# 9250.net
KiCad netlist of a schematic drawn in EAGLE
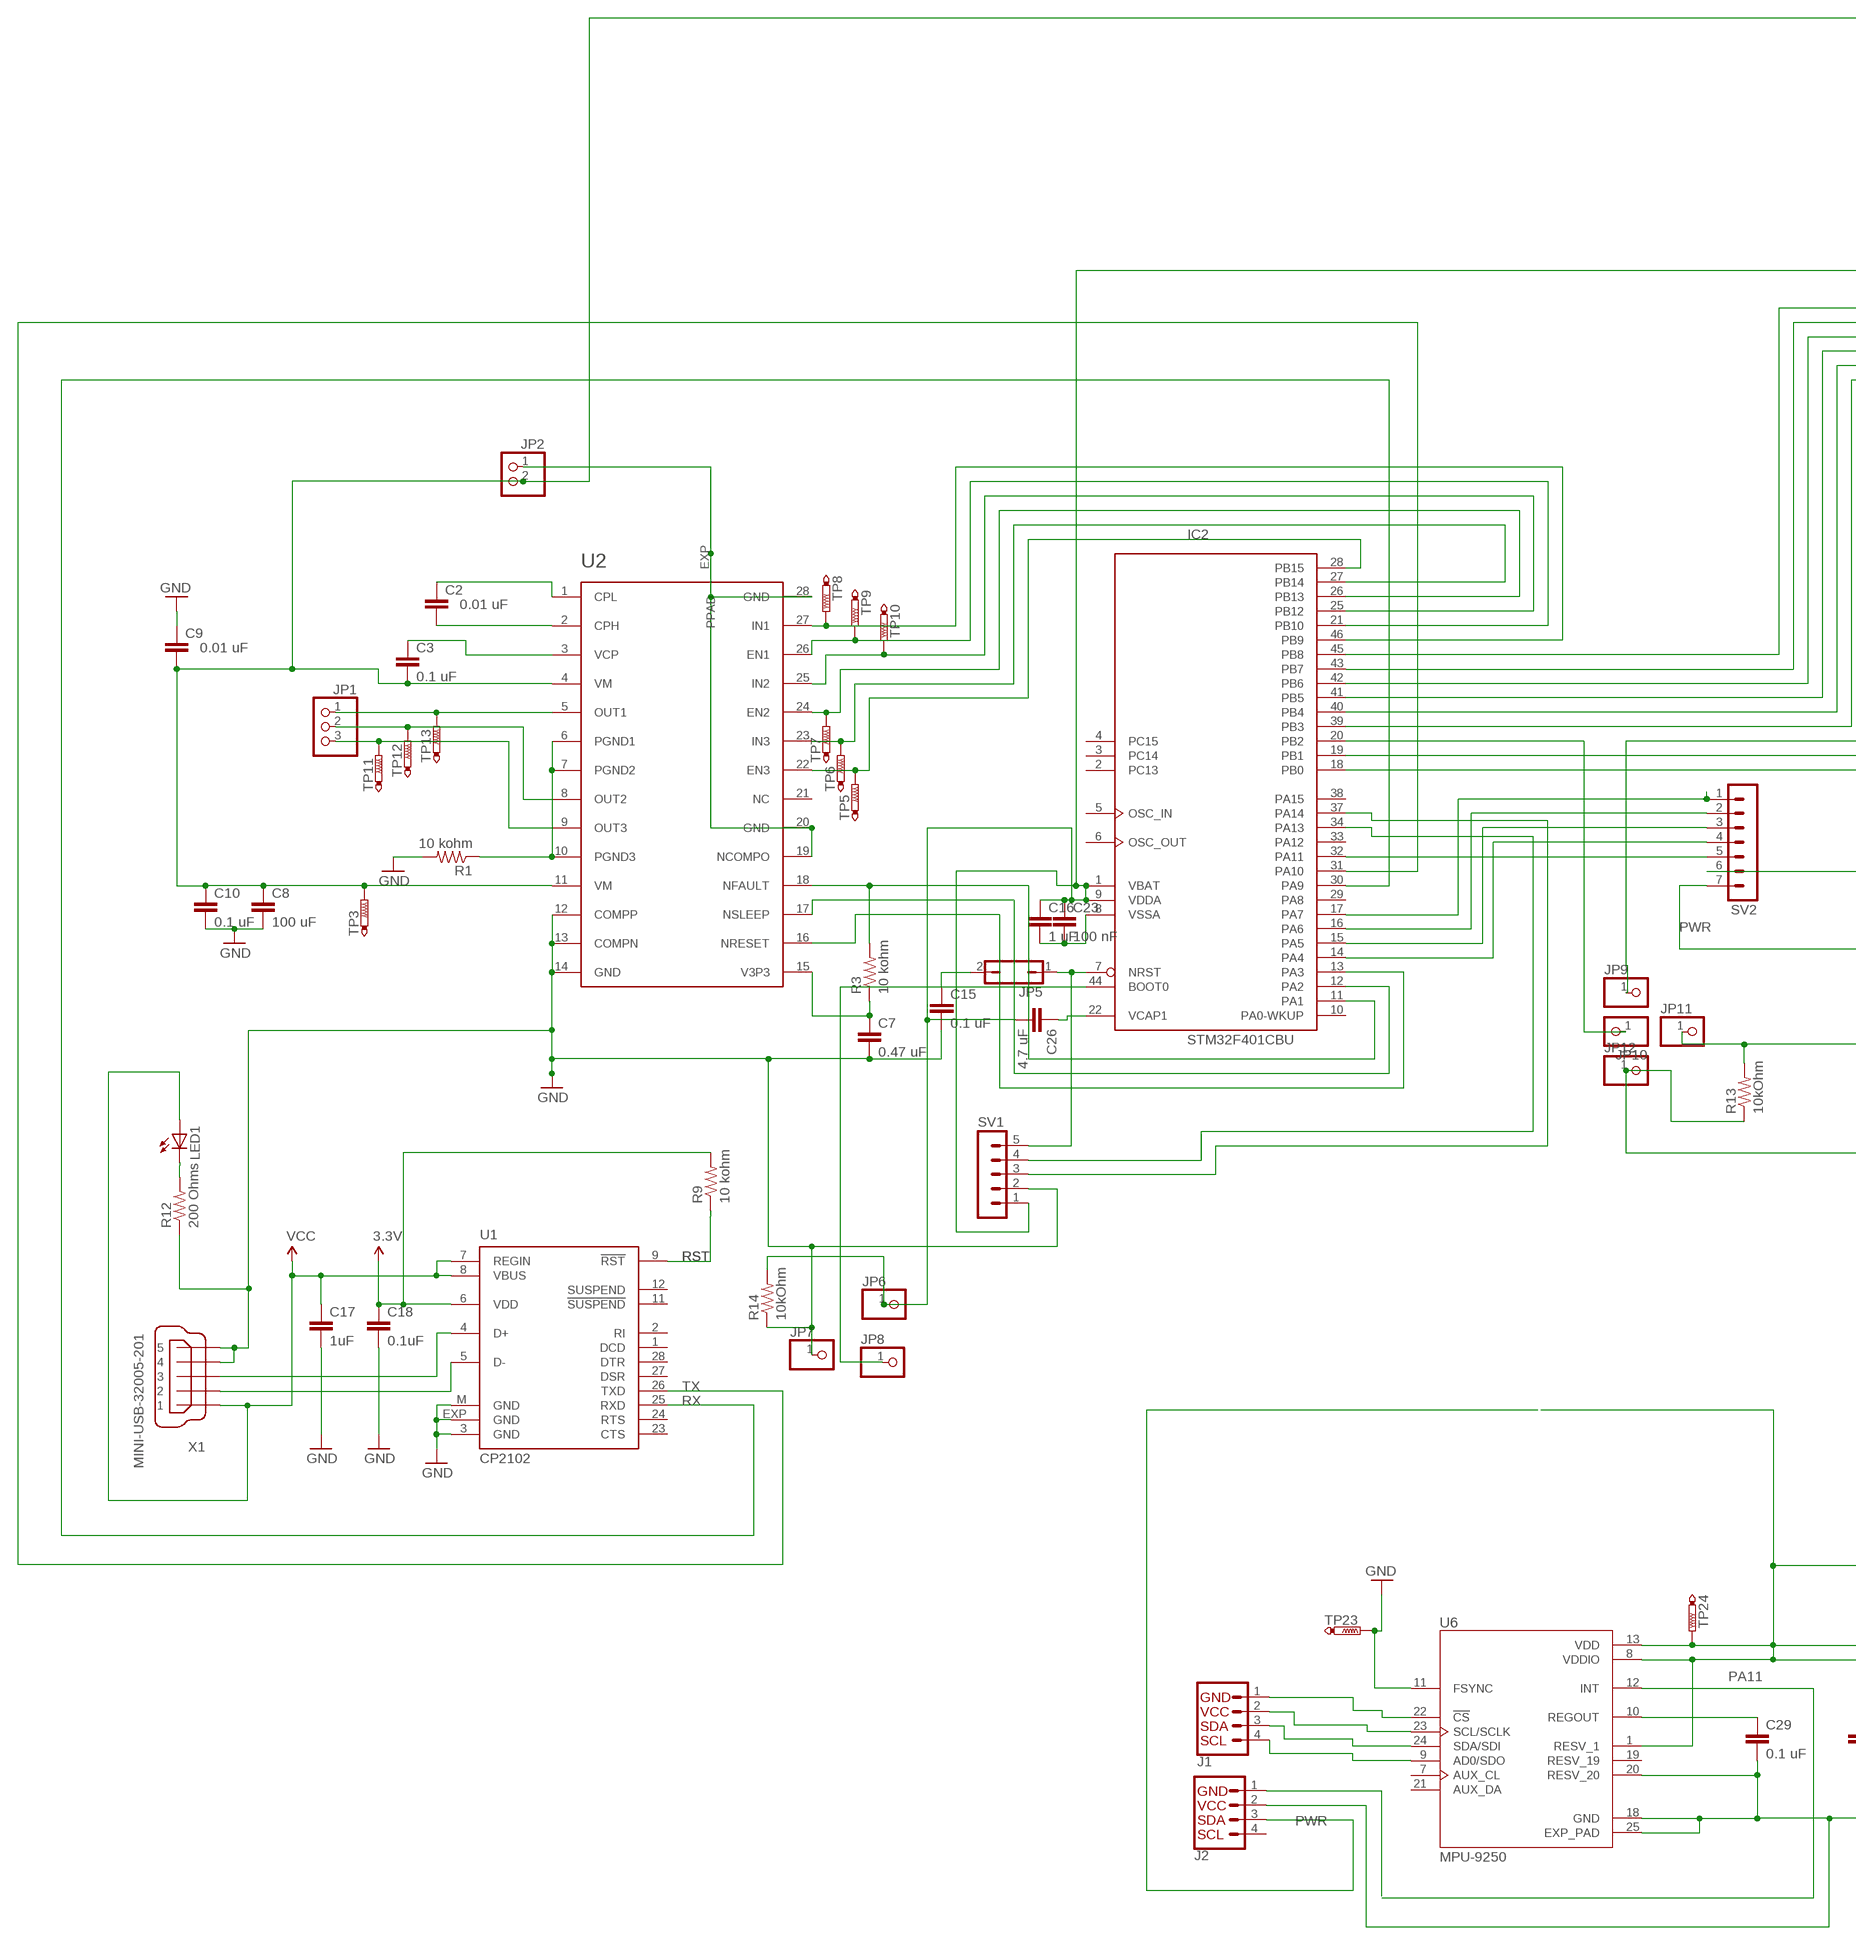
[diagram p0: schematic, sheet 1, part 1 of 2]
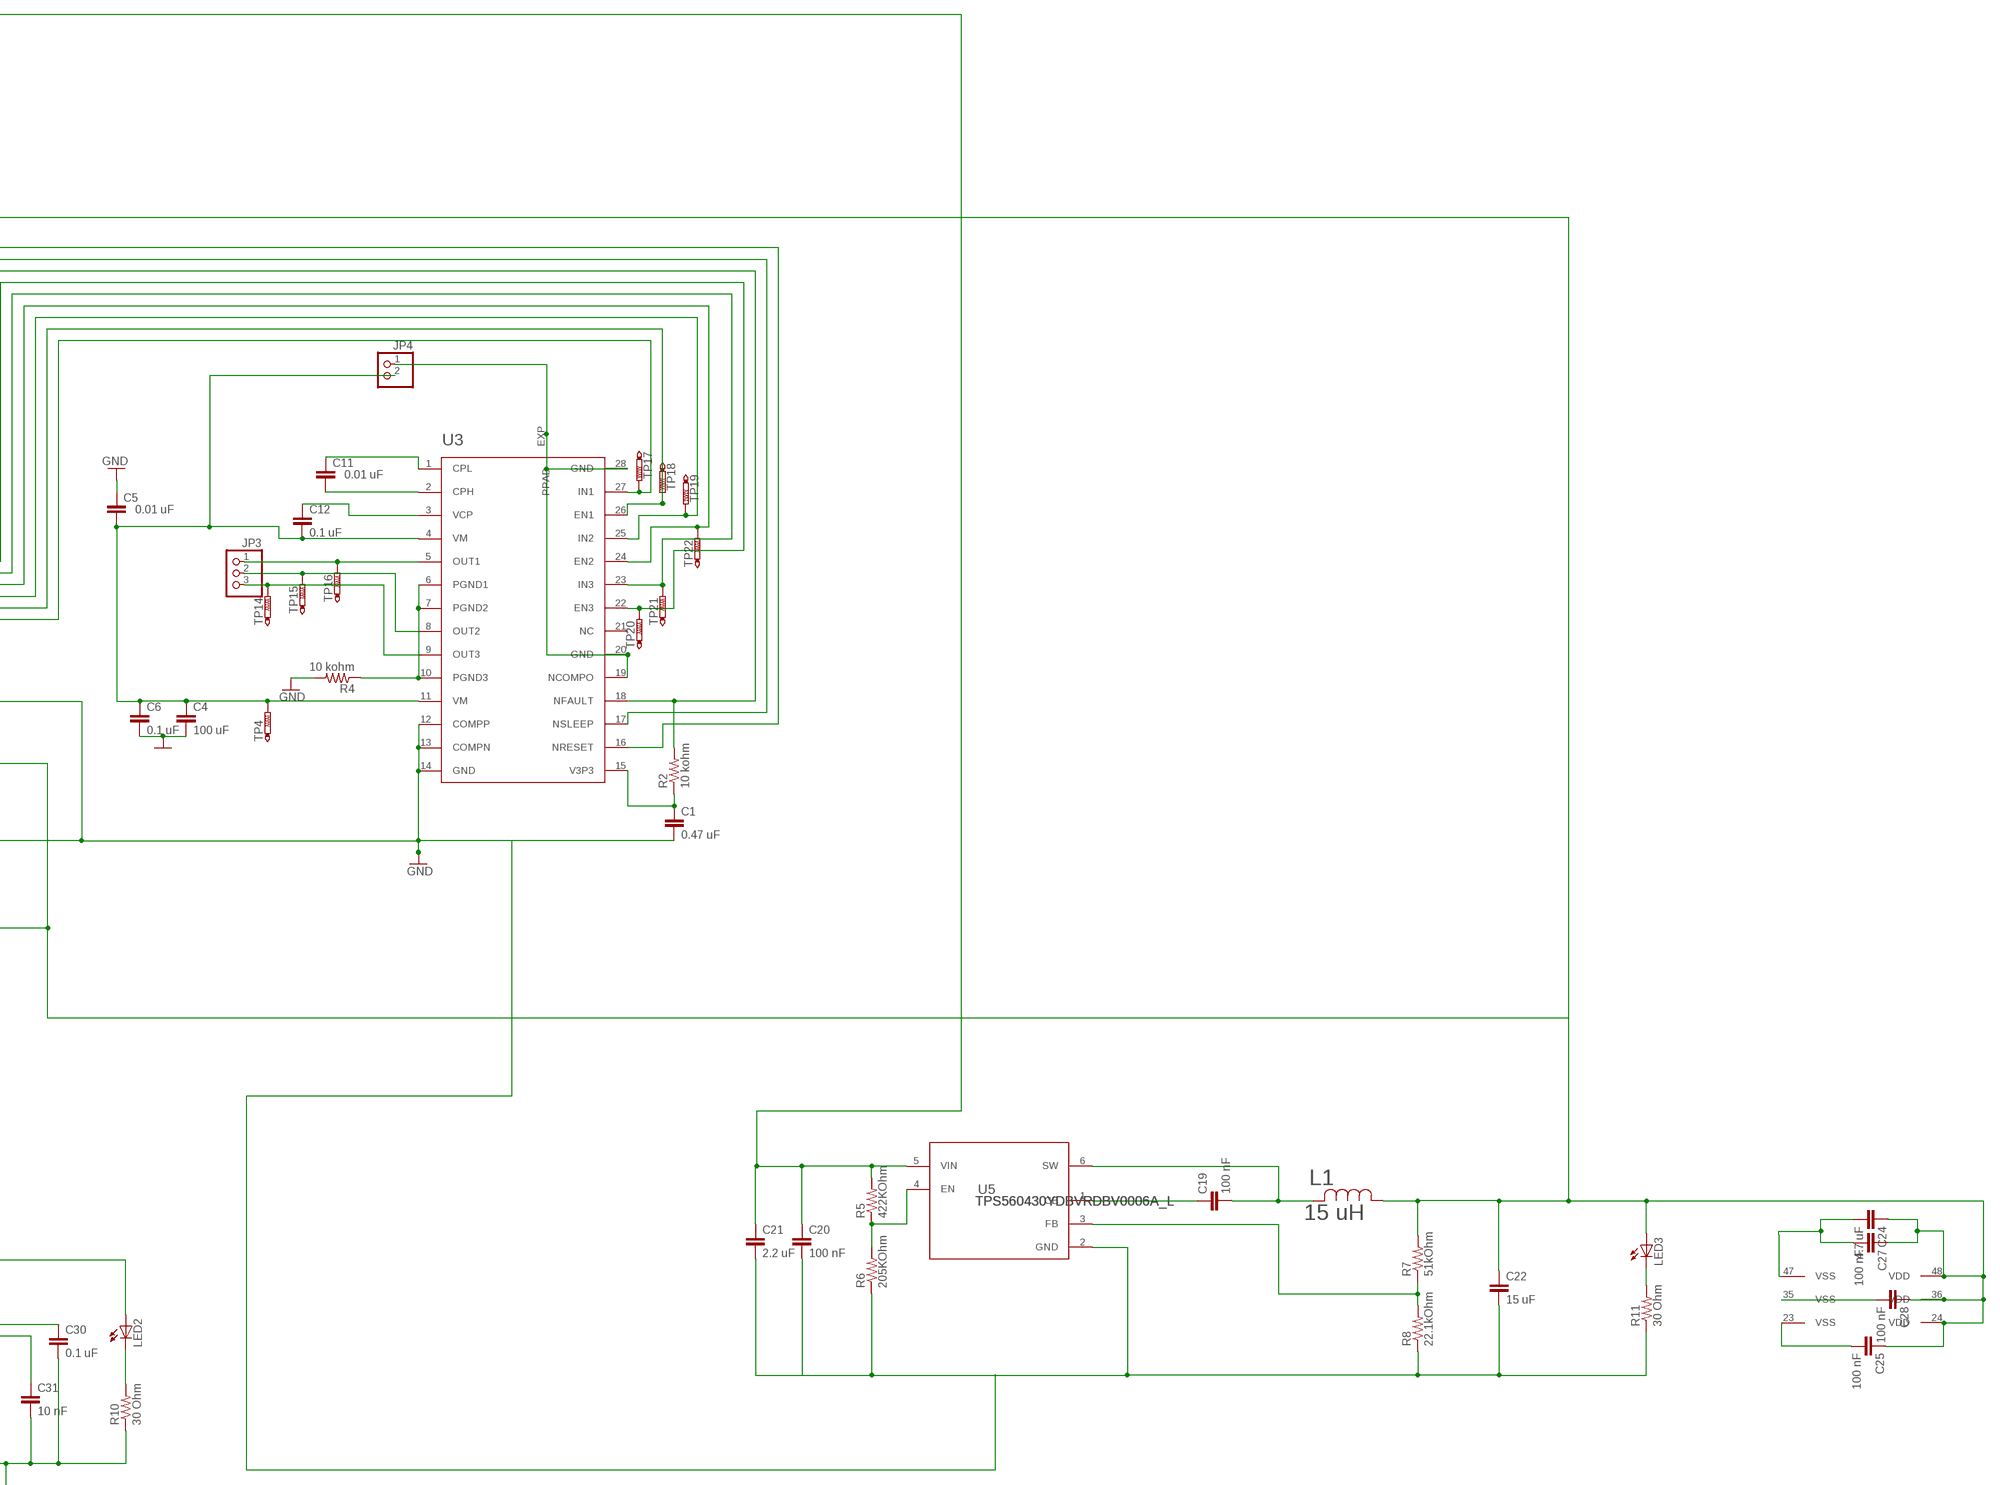
[diagram p1: schematic, sheet 1, part 2 of 2]

(export (version "E")
  (design (tool "Eeschema 10.0.6"))
  (components
    (comp (ref "C1")
      (value "0.47 uF")
      (footprint "eagle-import:C1210K")
      (libsource (lib "eagle-import") (part "C-EUC1210K"))
    )
    (comp (ref "C2")
      (value "0.01 uF")
      (footprint "eagle-import:C1210K")
      (libsource (lib "eagle-import") (part "C-EUC1210K"))
    )
    (comp (ref "C3")
      (value "0.1 uF")
      (footprint "eagle-import:C1210K")
      (libsource (lib "eagle-import") (part "C-EUC1210K"))
    )
    (comp (ref "C4")
      (value "100 uF")
      (footprint "eagle-import:C1210K")
      (libsource (lib "eagle-import") (part "C-EUC1210K"))
    )
    (comp (ref "C5")
      (value "0.01 uF")
      (footprint "eagle-import:C1210K")
      (libsource (lib "eagle-import") (part "C-EUC1210K"))
    )
    (comp (ref "C6")
      (value "0.1 uF")
      (footprint "eagle-import:C1210K")
      (libsource (lib "eagle-import") (part "C-EUC1210K"))
    )
    (comp (ref "C7")
      (value "0.47 uF")
      (footprint "eagle-import:C1210K")
      (libsource (lib "eagle-import") (part "C-EUC1210K"))
    )
    (comp (ref "C8")
      (value "100 uF")
      (footprint "eagle-import:C1210K")
      (libsource (lib "eagle-import") (part "C-EUC1210K"))
    )
    (comp (ref "C9")
      (value "0.01 uF")
      (footprint "eagle-import:C1210K")
      (libsource (lib "eagle-import") (part "C-EUC1210K"))
    )
    (comp (ref "C10")
      (value "0.1 uF")
      (footprint "eagle-import:C1210K")
      (libsource (lib "eagle-import") (part "C-EUC1210K"))
    )
    (comp (ref "C11")
      (value "0.01 uF")
      (footprint "eagle-import:C1210K")
      (libsource (lib "eagle-import") (part "C-EUC1210K"))
    )
    (comp (ref "C12")
      (value "0.1 uF")
      (footprint "eagle-import:C1210K")
      (libsource (lib "eagle-import") (part "C-EUC1210K"))
    )
    (comp (ref "C15")
      (value "0.1 uF")
      (footprint "eagle-import:C1210K")
      (libsource (lib "eagle-import") (part "C-EUC1210K"))
    )
    (comp (ref "C16")
      (value "1 uF")
      (footprint "eagle-import:C1210K")
      (libsource (lib "eagle-import") (part "C-EUC1210K"))
    )
    (comp (ref "C17")
      (value "1uF")
      (footprint "eagle-import:0603")
      (libsource (lib "eagle-import") (part "CAP0603"))
    )
    (comp (ref "C18")
      (value "0.1uF")
      (footprint "eagle-import:0603")
      (libsource (lib "eagle-import") (part "CAP0603"))
    )
    (comp (ref "C19")
      (value "100 nF")
      (footprint "eagle-import:C0402K")
      (libsource (lib "eagle-import") (part "C-EUC0402K"))
    )
    (comp (ref "C20")
      (value "100 nF")
      (footprint "eagle-import:C0402K")
      (libsource (lib "eagle-import") (part "C-EUC0402K"))
    )
    (comp (ref "C21")
      (value "2.2 uF")
      (footprint "eagle-import:C0402K")
      (libsource (lib "eagle-import") (part "C-EUC0402K"))
    )
    (comp (ref "C22")
      (value "15 uF")
      (footprint "eagle-import:C0402K")
      (libsource (lib "eagle-import") (part "C-EUC0402K"))
    )
    (comp (ref "C23")
      (value "100 nF")
      (footprint "eagle-import:C1210K")
      (libsource (lib "eagle-import") (part "C-EUC1210K"))
    )
    (comp (ref "C24")
      (value "4.7 uF")
      (footprint "eagle-import:C1210K")
      (libsource (lib "eagle-import") (part "C-EUC1210K"))
    )
    (comp (ref "C25")
      (value "100 nF")
      (footprint "eagle-import:C1210K")
      (libsource (lib "eagle-import") (part "C-EUC1210K"))
    )
    (comp (ref "C26")
      (value "4.7 uF")
      (footprint "eagle-import:C1210K")
      (libsource (lib "eagle-import") (part "C-EUC1210K"))
    )
    (comp (ref "C27")
      (value "100 nF")
      (footprint "eagle-import:C1210K")
      (libsource (lib "eagle-import") (part "C-EUC1210K"))
    )
    (comp (ref "C28")
      (value "100 nF")
      (footprint "eagle-import:C1210K")
      (libsource (lib "eagle-import") (part "C-EUC1210K"))
    )
    (comp (ref "C29")
      (value "0.1 uF")
      (footprint "eagle-import:C025-025X050")
      (libsource (lib "eagle-import") (part "C-EU025-025X050"))
    )
    (comp (ref "C30")
      (value "0.1 uF")
      (footprint "eagle-import:C025-025X050")
      (libsource (lib "eagle-import") (part "C-EU025-025X050"))
    )
    (comp (ref "C31")
      (value "10 nF")
      (footprint "eagle-import:C025-025X050")
      (libsource (lib "eagle-import") (part "C-EU025-025X050"))
    )
    (comp (ref "IC2")
      (value "STM32F401CBU")
      (footprint "eagle-import:UFQFPN48")
      (libsource (lib "eagle-import") (part "STM32F401CUB"))
    )
    (comp (ref "J1")
      (value "QWIIC_CONNECTORJS-1MM")
      (footprint "eagle-import:1X04_1MM_RA")
      (libsource (lib "eagle-import") (part "QWIIC_CONNECTORJS-1MM"))
    )
    (comp (ref "J2")
      (value "QWIIC_CONNECTORJS-1MM")
      (footprint "eagle-import:1X04_1MM_RA")
      (libsource (lib "eagle-import") (part "QWIIC_CONNECTORJS-1MM"))
    )
    (comp (ref "JP1")
      (value "PINHD-1X3/90")
      (footprint "eagle-import:1X03_90")
      (libsource (lib "eagle-import") (part "PINHD-1X3/90"))
    )
    (comp (ref "JP2")
      (value "PINHD-1X2/90")
      (footprint "eagle-import:1X02_90")
      (libsource (lib "eagle-import") (part "PINHD-1X2/90"))
    )
    (comp (ref "JP3")
      (value "PINHD-1X3/90")
      (footprint "eagle-import:1X03_90")
      (libsource (lib "eagle-import") (part "PINHD-1X3/90"))
    )
    (comp (ref "JP4")
      (value "PINHD-1X2/90")
      (footprint "eagle-import:1X02_90")
      (libsource (lib "eagle-import") (part "PINHD-1X2/90"))
    )
    (comp (ref "JP5")
      (value "JP1Q")
      (footprint "eagle-import:JP1")
      (libsource (lib "eagle-import") (part "JP1Q"))
    )
    (comp (ref "JP6")
      (value "PINHD-1X1")
      (footprint "eagle-import:1X01")
      (libsource (lib "eagle-import") (part "PINHD-1X1"))
    )
    (comp (ref "JP7")
      (value "PINHD-1X1")
      (footprint "eagle-import:1X01")
      (libsource (lib "eagle-import") (part "PINHD-1X1"))
    )
    (comp (ref "JP8")
      (value "PINHD-1X1")
      (footprint "eagle-import:1X01")
      (libsource (lib "eagle-import") (part "PINHD-1X1"))
    )
    (comp (ref "JP9")
      (value "PINHD-1X1")
      (footprint "eagle-import:1X01")
      (libsource (lib "eagle-import") (part "PINHD-1X1"))
    )
    (comp (ref "JP10")
      (value "PINHD-1X1")
      (footprint "eagle-import:1X01")
      (libsource (lib "eagle-import") (part "PINHD-1X1"))
    )
    (comp (ref "JP11")
      (value "PINHD-1X1")
      (footprint "eagle-import:1X01")
      (libsource (lib "eagle-import") (part "PINHD-1X1"))
    )
    (comp (ref "JP12")
      (value "PINHD-1X1")
      (footprint "eagle-import:1X01")
      (libsource (lib "eagle-import") (part "PINHD-1X1"))
    )
    (comp (ref "L1")
      (value "15 uH")
      (footprint "eagle-import:IND_BOURNS_SRN3015")
      (fields (field (name "MANUFACTURER_PART_NUMBER") "SRN3015150M"))
      (libsource (lib "eagle-import") (part "SRN3015-150M"))
    )
    (comp (ref "LED1")
      (value "LED_ESML0603")
      (footprint "eagle-import:LED_SML0603")
      (libsource (lib "eagle-import") (part "LED_ESML0603"))
    )
    (comp (ref "LED2")
      (value "LED_ESML0603")
      (footprint "eagle-import:LED_SML0603")
      (libsource (lib "eagle-import") (part "LED_ESML0603"))
    )
    (comp (ref "LED3")
      (value "LED_ESML0603")
      (footprint "eagle-import:LED_SML0603")
      (libsource (lib "eagle-import") (part "LED_ESML0603"))
    )
    (comp (ref "R1")
      (value "10 kohm")
      (footprint "eagle-import:M2012")
      (libsource (lib "eagle-import") (part "R-US_M2012"))
    )
    (comp (ref "R2")
      (value "10 kohm")
      (footprint "eagle-import:M2012")
      (libsource (lib "eagle-import") (part "R-US_M2012"))
    )
    (comp (ref "R3")
      (value "10 kohm")
      (footprint "eagle-import:M2012")
      (libsource (lib "eagle-import") (part "R-US_M2012"))
    )
    (comp (ref "R4")
      (value "10 kohm")
      (footprint "eagle-import:M2012")
      (libsource (lib "eagle-import") (part "R-US_M2012"))
    )
    (comp (ref "R5")
      (value "422KOhm")
      (footprint "eagle-import:M0805")
      (libsource (lib "eagle-import") (part "R-US_M0805"))
    )
    (comp (ref "R6")
      (value "205KOhm")
      (footprint "eagle-import:M0805")
      (libsource (lib "eagle-import") (part "R-US_M0805"))
    )
    (comp (ref "R7")
      (value "51kOhm")
      (footprint "eagle-import:M0805")
      (libsource (lib "eagle-import") (part "R-US_M0805"))
    )
    (comp (ref "R8")
      (value "22.1kOhm")
      (footprint "eagle-import:M0805")
      (libsource (lib "eagle-import") (part "R-US_M0805"))
    )
    (comp (ref "R9")
      (value "10 kohm")
      (footprint "eagle-import:M2012")
      (libsource (lib "eagle-import") (part "R-US_M2012"))
    )
    (comp (ref "R10")
      (value "30 Ohm")
      (footprint "eagle-import:M0805")
      (libsource (lib "eagle-import") (part "R-US_M0805"))
    )
    (comp (ref "R11")
      (value "30 Ohm")
      (footprint "eagle-import:M0805")
      (libsource (lib "eagle-import") (part "R-US_M0805"))
    )
    (comp (ref "R12")
      (value "200 Ohms")
      (footprint "eagle-import:M0805")
      (libsource (lib "eagle-import") (part "R-US_M0805"))
    )
    (comp (ref "R13")
      (value "10kOhm")
      (footprint "eagle-import:M0805")
      (libsource (lib "eagle-import") (part "R-US_M0805"))
    )
    (comp (ref "R14")
      (value "10kOhm")
      (footprint "eagle-import:M0805")
      (libsource (lib "eagle-import") (part "R-US_M0805"))
    )
    (comp (ref "SV1")
      (value "MA05-1")
      (footprint "eagle-import:MA05-1")
      (libsource (lib "eagle-import") (part "MA05-1"))
    )
    (comp (ref "SV2")
      (value "MA07-1")
      (footprint "eagle-import:MA07-1")
      (libsource (lib "eagle-import") (part "MA07-1"))
    )
    (comp (ref "TP3")
      (value "PTR1TP12R")
      (footprint "eagle-import:TP12R")
      (libsource (lib "eagle-import") (part "PTR1TP12R"))
    )
    (comp (ref "TP4")
      (value "PTR1TP12R")
      (footprint "eagle-import:TP12R")
      (libsource (lib "eagle-import") (part "PTR1TP12R"))
    )
    (comp (ref "TP5")
      (value "PTR1TP12R")
      (footprint "eagle-import:TP12R")
      (libsource (lib "eagle-import") (part "PTR1TP12R"))
    )
    (comp (ref "TP6")
      (value "PTR1TP12R")
      (footprint "eagle-import:TP12R")
      (libsource (lib "eagle-import") (part "PTR1TP12R"))
    )
    (comp (ref "TP7")
      (value "PTR1TP12R")
      (footprint "eagle-import:TP12R")
      (libsource (lib "eagle-import") (part "PTR1TP12R"))
    )
    (comp (ref "TP8")
      (value "PTR1TP12R")
      (footprint "eagle-import:TP12R")
      (libsource (lib "eagle-import") (part "PTR1TP12R"))
    )
    (comp (ref "TP9")
      (value "PTR1TP12R")
      (footprint "eagle-import:TP12R")
      (libsource (lib "eagle-import") (part "PTR1TP12R"))
    )
    (comp (ref "TP10")
      (value "PTR1TP12R")
      (footprint "eagle-import:TP12R")
      (libsource (lib "eagle-import") (part "PTR1TP12R"))
    )
    (comp (ref "TP11")
      (value "PTR1TP12R")
      (footprint "eagle-import:TP12R")
      (libsource (lib "eagle-import") (part "PTR1TP12R"))
    )
    (comp (ref "TP12")
      (value "PTR1TP12R")
      (footprint "eagle-import:TP12R")
      (libsource (lib "eagle-import") (part "PTR1TP12R"))
    )
    (comp (ref "TP13")
      (value "PTR1TP12R")
      (footprint "eagle-import:TP12R")
      (libsource (lib "eagle-import") (part "PTR1TP12R"))
    )
    (comp (ref "TP14")
      (value "PTR1TP12R")
      (footprint "eagle-import:TP12R")
      (libsource (lib "eagle-import") (part "PTR1TP12R"))
    )
    (comp (ref "TP15")
      (value "PTR1TP12R")
      (footprint "eagle-import:TP12R")
      (libsource (lib "eagle-import") (part "PTR1TP12R"))
    )
    (comp (ref "TP16")
      (value "PTR1TP12R")
      (footprint "eagle-import:TP12R")
      (libsource (lib "eagle-import") (part "PTR1TP12R"))
    )
    (comp (ref "TP17")
      (value "PTR1TP12R")
      (footprint "eagle-import:TP12R")
      (libsource (lib "eagle-import") (part "PTR1TP12R"))
    )
    (comp (ref "TP18")
      (value "PTR1TP12R")
      (footprint "eagle-import:TP12R")
      (libsource (lib "eagle-import") (part "PTR1TP12R"))
    )
    (comp (ref "TP19")
      (value "PTR1TP12R")
      (footprint "eagle-import:TP12R")
      (libsource (lib "eagle-import") (part "PTR1TP12R"))
    )
    (comp (ref "TP20")
      (value "PTR1TP12R")
      (footprint "eagle-import:TP12R")
      (libsource (lib "eagle-import") (part "PTR1TP12R"))
    )
    (comp (ref "TP21")
      (value "PTR1TP12R")
      (footprint "eagle-import:TP12R")
      (libsource (lib "eagle-import") (part "PTR1TP12R"))
    )
    (comp (ref "TP22")
      (value "PTR1TP12R")
      (footprint "eagle-import:TP12R")
      (libsource (lib "eagle-import") (part "PTR1TP12R"))
    )
    (comp (ref "TP23")
      (value "PTR1TP12R")
      (footprint "eagle-import:TP12R")
      (libsource (lib "eagle-import") (part "PTR1TP12R"))
    )
    (comp (ref "TP24")
      (value "PTR1TP12R")
      (footprint "eagle-import:TP12R")
      (libsource (lib "eagle-import") (part "PTR1TP12R"))
    )
    (comp (ref "U1")
      (value "CP2102")
      (footprint "eagle-import:MLP28")
      (libsource (lib "eagle-import") (part "CP210X_USB_UART"))
    )
    (comp (ref "U2")
      (value "DRV8313PWPR")
      (footprint "eagle-import:HTSSOP28PWP")
      (libsource (lib "eagle-import") (part "DRV8313PWPR"))
    )
    (comp (ref "U3")
      (value "DRV8313PWPR")
      (footprint "eagle-import:HTSSOP28PWP")
      (libsource (lib "eagle-import") (part "DRV8313PWPR"))
    )
    (comp (ref "U5")
      (value "TPS560430YDBVRDBV0006A_L")
      (footprint "eagle-import:DBV0006A_L")
      (libsource (lib "eagle-import") (part "TPS560430YDBVRDBV0006A_L"))
    )
    (comp (ref "U6")
      (value "MPU-9250")
      (footprint "eagle-import:QFN40P300X300X105-25N")
      (fields (field (name "MF") "TDK InvenSense"))
      (libsource (lib "eagle-import") (part "MPU-9250"))
    )
    (comp (ref "X1")
      (value "MINI-USB-32005-201")
      (footprint "eagle-import:32005-201")
      (libsource (lib "eagle-import") (part "MINI-USB-32005-201"))
    )
  )
  (nets
    (net (code "1") (name "/PA11") (class "Default")
      (node (ref "U6") (pin "12") (pinfunction "INT_12") (pintype "output"))
    )
    (net (code "2") (name "/PWR") (class "Default")
      (node (ref "C16") (pin "1") (pinfunction "1_1") (pintype "passive"))
      (node (ref "C22") (pin "1") (pinfunction "1_1") (pintype "passive"))
      (node (ref "C23") (pin "1") (pinfunction "1_1") (pintype "passive"))
      (node (ref "C24") (pin "1") (pinfunction "1_1") (pintype "passive"))
      (node (ref "C25") (pin "1") (pinfunction "1_1") (pintype "passive"))
      (node (ref "C26") (pin "2") (pinfunction "2_2") (pintype "passive"))
      (node (ref "C27") (pin "1") (pinfunction "1_1") (pintype "passive"))
      (node (ref "C28") (pin "1") (pinfunction "1_1") (pintype "passive"))
      (node (ref "IC2") (pin "1") (pinfunction "VBAT_1") (pintype "power_in"))
      (node (ref "IC2") (pin "24") (pinfunction "VDD_24") (pintype "power_in"))
      (node (ref "IC2") (pin "36") (pinfunction "VDD_36") (pintype "power_in"))
      (node (ref "IC2") (pin "48") (pinfunction "VDD_48") (pintype "power_in"))
      (node (ref "IC2") (pin "9") (pinfunction "VDDA_9") (pintype "power_in"))
      (node (ref "J2") (pin "3") (pinfunction "3_3") (pintype "passive"))
      (node (ref "JP12") (pin "1") (pinfunction "1_1") (pintype "passive"))
      (node (ref "JP6") (pin "1") (pinfunction "1_1") (pintype "passive"))
      (node (ref "L1") (pin "1") (pinfunction "1_1") (pintype "passive"))
      (node (ref "LED3") (pin "A") (pinfunction "A_A") (pintype "passive"))
      (node (ref "R13") (pin "1") (pinfunction "1_1") (pintype "passive"))
      (node (ref "R14") (pin "2") (pinfunction "2_2") (pintype "passive"))
      (node (ref "R7") (pin "2") (pinfunction "2_2") (pintype "passive"))
      (node (ref "SV1") (pin "1") (pinfunction "1_1") (pintype "passive"))
      (node (ref "SV2") (pin "7") (pinfunction "7_7") (pintype "passive"))
    )
    (net (code "3") (name "/RST") (class "Default")
      (node (ref "R9") (pin "1") (pinfunction "1_1") (pintype "passive"))
      (node (ref "U1") (pin "9") (pinfunction "~{RST}_9") (pintype "bidirectional"))
    )
    (net (code "4") (name "/RX") (class "Default")
      (node (ref "IC2") (pin "34") (pinfunction "PA13_34") (pintype "bidirectional"))
      (node (ref "SV1") (pin "4") (pinfunction "4_4") (pintype "passive"))
    )
    (net (code "5") (name "/TX") (class "Default")
      (node (ref "IC2") (pin "37") (pinfunction "PA14_37") (pintype "bidirectional"))
      (node (ref "SV1") (pin "3") (pinfunction "3_3") (pintype "passive"))
    )
    (net (code "6") (name "3.3V") (class "Default")
      (node (ref "C18") (pin "1") (pinfunction "1_1") (pintype "passive"))
      (node (ref "R9") (pin "2") (pinfunction "2_2") (pintype "passive"))
      (node (ref "U1") (pin "6") (pinfunction "VDD_6") (pintype "power_in"))
    )
    (net (code "7") (name "GND") (class "Default")
      (node (ref "C1") (pin "2") (pinfunction "2_2") (pintype "passive"))
      (node (ref "C10") (pin "2") (pinfunction "2_2") (pintype "passive"))
      (node (ref "C15") (pin "2") (pinfunction "2_2") (pintype "passive"))
      (node (ref "C17") (pin "2") (pinfunction "2_2") (pintype "passive"))
      (node (ref "C18") (pin "2") (pinfunction "2_2") (pintype "passive"))
      (node (ref "C4") (pin "2") (pinfunction "2_2") (pintype "passive"))
      (node (ref "C5") (pin "1") (pinfunction "1_1") (pintype "passive"))
      (node (ref "C6") (pin "2") (pinfunction "2_2") (pintype "passive"))
      (node (ref "C7") (pin "2") (pinfunction "2_2") (pintype "passive"))
      (node (ref "C8") (pin "2") (pinfunction "2_2") (pintype "passive"))
      (node (ref "C9") (pin "1") (pinfunction "1_1") (pintype "passive"))
      (node (ref "JP11") (pin "1") (pinfunction "1_1") (pintype "passive"))
      (node (ref "JP2") (pin "1") (pinfunction "1_1") (pintype "passive"))
      (node (ref "JP4") (pin "1") (pinfunction "1_1") (pintype "passive"))
      (node (ref "JP7") (pin "1") (pinfunction "1_1") (pintype "passive"))
      (node (ref "R1") (pin "2") (pinfunction "2_2") (pintype "passive"))
      (node (ref "R12") (pin "1") (pinfunction "1_1") (pintype "passive"))
      (node (ref "R13") (pin "2") (pinfunction "2_2") (pintype "passive"))
      (node (ref "R14") (pin "1") (pinfunction "1_1") (pintype "passive"))
      (node (ref "R4") (pin "2") (pinfunction "2_2") (pintype "passive"))
      (node (ref "SV1") (pin "2") (pinfunction "2_2") (pintype "passive"))
      (node (ref "SV2") (pin "6") (pinfunction "6_6") (pintype "passive"))
      (node (ref "TP23") (pin "TP") (pinfunction "TP_TP") (pintype "input"))
      (node (ref "U1") (pin "3") (pinfunction "GND_3") (pintype "power_in"))
      (node (ref "U1") (pin "EXP") (pinfunction "GND_EXP") (pintype "power_in"))
      (node (ref "U1") (pin "M") (pinfunction "GND_M") (pintype "power_in"))
      (node (ref "U2") (pin "12") (pinfunction "COMPP_12") (pintype "input"))
      (node (ref "U2") (pin "13") (pinfunction "COMPN_13") (pintype "input"))
      (node (ref "U2") (pin "14") (pinfunction "GND_14") (pintype "power_in"))
      (node (ref "U2") (pin "19") (pinfunction "NCOMPO_19") (pintype "open_collector"))
      (node (ref "U2") (pin "20") (pinfunction "GND_20") (pintype "power_in"))
      (node (ref "U2") (pin "28") (pinfunction "GND_28") (pintype "power_in"))
      (node (ref "U2") (pin "EXP") (pinfunction "PPAD_EXP") (pintype "power_in"))
      (node (ref "U3") (pin "12") (pinfunction "COMPP_12") (pintype "input"))
      (node (ref "U3") (pin "13") (pinfunction "COMPN_13") (pintype "input"))
      (node (ref "U3") (pin "14") (pinfunction "GND_14") (pintype "power_in"))
      (node (ref "U3") (pin "19") (pinfunction "NCOMPO_19") (pintype "open_collector"))
      (node (ref "U3") (pin "20") (pinfunction "GND_20") (pintype "power_in"))
      (node (ref "U3") (pin "28") (pinfunction "GND_28") (pintype "power_in"))
      (node (ref "U3") (pin "EXP") (pinfunction "PPAD_EXP") (pintype "power_in"))
      (node (ref "U6") (pin "11") (pinfunction "FSYNC_11") (pintype "input"))
      (node (ref "X1") (pin "4") (pinfunction "4_4") (pintype "passive"))
      (node (ref "X1") (pin "5") (pinfunction "5_5") (pintype "passive"))
    )
    (net (code "8") (name "Net-(C12-Pad2)") (class "Default")
      (node (ref "C12") (pin "2") (pinfunction "2_2") (pintype "passive"))
      (node (ref "C4") (pin "1") (pinfunction "1_1") (pintype "passive"))
      (node (ref "C5") (pin "2") (pinfunction "2_2") (pintype "passive"))
      (node (ref "C6") (pin "1") (pinfunction "1_1") (pintype "passive"))
      (node (ref "JP4") (pin "2") (pinfunction "2_2") (pintype "passive"))
      (node (ref "TP4") (pin "TP") (pinfunction "TP_TP") (pintype "input"))
      (node (ref "U3") (pin "11") (pinfunction "VM_11") (pintype "power_in"))
      (node (ref "U3") (pin "4") (pinfunction "VM_4") (pintype "power_in"))
    )
    (net (code "9") (name "Net-(C15-Pad1)") (class "Default")
      (node (ref "C15") (pin "1") (pinfunction "1_1") (pintype "passive"))
      (node (ref "JP5") (pin "2") (pinfunction "2_2") (pintype "passive"))
    )
    (net (code "10") (name "Net-(C24-Pad2)") (class "Default")
      (node (ref "C24") (pin "2") (pinfunction "2_2") (pintype "passive"))
      (node (ref "C27") (pin "2") (pinfunction "2_2") (pintype "passive"))
      (node (ref "IC2") (pin "47") (pinfunction "VSS_47") (pintype "power_in"))
    )
    (net (code "11") (name "Net-(C25-Pad2)") (class "Default")
      (node (ref "C25") (pin "2") (pinfunction "2_2") (pintype "passive"))
      (node (ref "IC2") (pin "23") (pinfunction "VSS_23") (pintype "power_in"))
    )
    (net (code "12") (name "Net-(C28-Pad2)") (class "Default")
      (node (ref "C28") (pin "2") (pinfunction "2_2") (pintype "passive"))
      (node (ref "IC2") (pin "35") (pinfunction "VSS_35") (pintype "power_in"))
    )
    (net (code "13") (name "Net-(IC2A-BOOT0)") (class "Default")
      (node (ref "IC2") (pin "44") (pinfunction "BOOT0_44") (pintype "input"))
      (node (ref "JP8") (pin "1") (pinfunction "1_1") (pintype "passive"))
    )
    (net (code "14") (name "Net-(IC2A-NRST)") (class "Default")
      (node (ref "IC2") (pin "7") (pinfunction "NRST_7") (pintype "bidirectional"))
      (node (ref "JP5") (pin "1") (pinfunction "1_1") (pintype "passive"))
      (node (ref "SV1") (pin "5") (pinfunction "5_5") (pintype "passive"))
    )
    (net (code "15") (name "Net-(IC2A-PA1)") (class "Default")
      (node (ref "IC2") (pin "11") (pinfunction "PA1_11") (pintype "bidirectional"))
      (node (ref "R3") (pin "2") (pinfunction "2_2") (pintype "passive"))
      (node (ref "U2") (pin "18") (pinfunction "NFAULT_18") (pintype "open_collector"))
    )
    (net (code "16") (name "Net-(IC2A-PA2)") (class "Default")
      (node (ref "IC2") (pin "12") (pinfunction "PA2_12") (pintype "bidirectional"))
      (node (ref "U2") (pin "17") (pinfunction "NSLEEP_17") (pintype "input"))
    )
    (net (code "17") (name "Net-(IC2A-PA3)") (class "Default")
      (node (ref "IC2") (pin "13") (pinfunction "PA3_13") (pintype "bidirectional"))
      (node (ref "U2") (pin "16") (pinfunction "NRESET_16") (pintype "input"))
    )
    (net (code "18") (name "Net-(IC2A-PA4)") (class "Default")
      (node (ref "IC2") (pin "14") (pinfunction "PA4_14") (pintype "bidirectional"))
      (node (ref "SV2") (pin "4") (pinfunction "4_4") (pintype "passive"))
    )
    (net (code "19") (name "Net-(IC2A-PA5)") (class "Default")
      (node (ref "IC2") (pin "15") (pinfunction "PA5_15") (pintype "bidirectional"))
      (node (ref "SV2") (pin "3") (pinfunction "3_3") (pintype "passive"))
    )
    (net (code "20") (name "Net-(IC2A-PA6)") (class "Default")
      (node (ref "IC2") (pin "16") (pinfunction "PA6_16") (pintype "bidirectional"))
      (node (ref "SV2") (pin "2") (pinfunction "2_2") (pintype "passive"))
    )
    (net (code "21") (name "Net-(IC2A-PA7)") (class "Default")
      (node (ref "IC2") (pin "17") (pinfunction "PA7_17") (pintype "bidirectional"))
      (node (ref "SV2") (pin "1") (pinfunction "1_1") (pintype "passive"))
    )
    (net (code "22") (name "Net-(IC2A-PA9)") (class "Default")
      (node (ref "IC2") (pin "30") (pinfunction "PA9_30") (pintype "bidirectional"))
      (node (ref "U1") (pin "25") (pinfunction "RXD_25") (pintype "input"))
    )
    (net (code "23") (name "Net-(IC2A-PA10)") (class "Default")
      (node (ref "IC2") (pin "31") (pinfunction "PA10_31") (pintype "bidirectional"))
      (node (ref "U1") (pin "26") (pinfunction "TXD_26") (pintype "output"))
    )
    (net (code "24") (name "Net-(IC2A-PA11)") (class "Default")
      (node (ref "IC2") (pin "32") (pinfunction "PA11_32") (pintype "bidirectional"))
      (node (ref "SV2") (pin "5") (pinfunction "5_5") (pintype "passive"))
    )
    (net (code "25") (name "Net-(IC2A-PB0)") (class "Default")
      (node (ref "IC2") (pin "18") (pinfunction "PB0_18") (pintype "bidirectional"))
      (node (ref "TP17") (pin "TP") (pinfunction "TP_TP") (pintype "input"))
      (node (ref "U3") (pin "27") (pinfunction "IN1_27") (pintype "input"))
    )
    (net (code "26") (name "Net-(IC2A-PB1)") (class "Default")
      (node (ref "IC2") (pin "19") (pinfunction "PB1_19") (pintype "bidirectional"))
      (node (ref "TP18") (pin "TP") (pinfunction "TP_TP") (pintype "input"))
      (node (ref "U3") (pin "26") (pinfunction "EN1_26") (pintype "input"))
    )
    (net (code "27") (name "Net-(IC2A-PB2)") (class "Default")
      (node (ref "IC2") (pin "20") (pinfunction "PB2_20") (pintype "bidirectional"))
      (node (ref "JP10") (pin "1") (pinfunction "1_1") (pintype "passive"))
    )
    (net (code "28") (name "Net-(IC2A-PB3)") (class "Default")
      (node (ref "IC2") (pin "39") (pinfunction "PB3_39") (pintype "bidirectional"))
      (node (ref "TP22") (pin "TP") (pinfunction "TP_TP") (pintype "input"))
      (node (ref "U3") (pin "24") (pinfunction "EN2_24") (pintype "input"))
    )
    (net (code "29") (name "Net-(IC2A-PB4)") (class "Default")
      (node (ref "IC2") (pin "40") (pinfunction "PB4_40") (pintype "bidirectional"))
      (node (ref "TP21") (pin "TP") (pinfunction "TP_TP") (pintype "input"))
      (node (ref "U3") (pin "23") (pinfunction "IN3_23") (pintype "input"))
    )
    (net (code "30") (name "Net-(IC2A-PB5)") (class "Default")
      (node (ref "IC2") (pin "41") (pinfunction "PB5_41") (pintype "bidirectional"))
      (node (ref "TP20") (pin "TP") (pinfunction "TP_TP") (pintype "input"))
      (node (ref "U3") (pin "22") (pinfunction "EN3_22") (pintype "input"))
    )
    (net (code "31") (name "Net-(IC2A-PB6)") (class "Default")
      (node (ref "IC2") (pin "42") (pinfunction "PB6_42") (pintype "bidirectional"))
      (node (ref "R2") (pin "2") (pinfunction "2_2") (pintype "passive"))
      (node (ref "U3") (pin "18") (pinfunction "NFAULT_18") (pintype "open_collector"))
    )
    (net (code "32") (name "Net-(IC2A-PB7)") (class "Default")
      (node (ref "IC2") (pin "43") (pinfunction "PB7_43") (pintype "bidirectional"))
      (node (ref "U3") (pin "17") (pinfunction "NSLEEP_17") (pintype "input"))
    )
    (net (code "33") (name "Net-(IC2A-PB8)") (class "Default")
      (node (ref "IC2") (pin "45") (pinfunction "PB8_45") (pintype "bidirectional"))
      (node (ref "U3") (pin "16") (pinfunction "NRESET_16") (pintype "input"))
    )
    (net (code "34") (name "Net-(IC2A-PB9)") (class "Default")
      (node (ref "IC2") (pin "46") (pinfunction "PB9_46") (pintype "bidirectional"))
      (node (ref "TP8") (pin "TP") (pinfunction "TP_TP") (pintype "input"))
      (node (ref "U2") (pin "27") (pinfunction "IN1_27") (pintype "input"))
    )
    (net (code "35") (name "Net-(IC2A-PB10)") (class "Default")
      (node (ref "IC2") (pin "21") (pinfunction "PB10_21") (pintype "bidirectional"))
      (node (ref "TP9") (pin "TP") (pinfunction "TP_TP") (pintype "input"))
      (node (ref "U2") (pin "26") (pinfunction "EN1_26") (pintype "input"))
    )
    (net (code "36") (name "Net-(IC2A-PB12)") (class "Default")
      (node (ref "IC2") (pin "25") (pinfunction "PB12_25") (pintype "bidirectional"))
      (node (ref "TP10") (pin "TP") (pinfunction "TP_TP") (pintype "input"))
      (node (ref "U2") (pin "25") (pinfunction "IN2_25") (pintype "input"))
    )
    (net (code "37") (name "Net-(IC2A-PB13)") (class "Default")
      (node (ref "IC2") (pin "26") (pinfunction "PB13_26") (pintype "bidirectional"))
      (node (ref "TP7") (pin "TP") (pinfunction "TP_TP") (pintype "input"))
      (node (ref "U2") (pin "24") (pinfunction "EN2_24") (pintype "input"))
    )
    (net (code "38") (name "Net-(IC2A-PB14)") (class "Default")
      (node (ref "IC2") (pin "27") (pinfunction "PB14_27") (pintype "bidirectional"))
      (node (ref "TP6") (pin "TP") (pinfunction "TP_TP") (pintype "input"))
      (node (ref "U2") (pin "23") (pinfunction "IN3_23") (pintype "input"))
    )
    (net (code "39") (name "Net-(IC2A-PB15)") (class "Default")
      (node (ref "IC2") (pin "28") (pinfunction "PB15_28") (pintype "bidirectional"))
      (node (ref "TP5") (pin "TP") (pinfunction "TP_TP") (pintype "input"))
      (node (ref "U2") (pin "22") (pinfunction "EN3_22") (pintype "input"))
    )
    (net (code "40") (name "Net-(IC2A-VCAP1)") (class "Default")
      (node (ref "C26") (pin "1") (pinfunction "1_1") (pintype "passive"))
      (node (ref "IC2") (pin "22") (pinfunction "VCAP1_22") (pintype "power_in"))
    )
    (net (code "41") (name "Net-(IC2A-VSSA)") (class "Default")
      (node (ref "C16") (pin "2") (pinfunction "2_2") (pintype "passive"))
      (node (ref "C23") (pin "2") (pinfunction "2_2") (pintype "passive"))
      (node (ref "IC2") (pin "8") (pinfunction "VSSA_8") (pintype "power_in"))
    )
    (net (code "42") (name "Net-(LED1-PadC)") (class "Default")
      (node (ref "LED1") (pin "C") (pinfunction "C_C") (pintype "passive"))
      (node (ref "R12") (pin "2") (pinfunction "2_2") (pintype "passive"))
    )
    (net (code "43") (name "Net-(LED2-PadC)") (class "Default")
      (node (ref "LED2") (pin "C") (pinfunction "C_C") (pintype "passive"))
      (node (ref "R10") (pin "2") (pinfunction "2_2") (pintype "passive"))
    )
    (net (code "44") (name "Net-(LED3-PadC)") (class "Default")
      (node (ref "LED3") (pin "C") (pinfunction "C_C") (pintype "passive"))
      (node (ref "R11") (pin "2") (pinfunction "2_2") (pintype "passive"))
    )
    (net (code "45") (name "Net-(U1-D+)") (class "Default")
      (node (ref "U1") (pin "4") (pinfunction "D+_4") (pintype "bidirectional"))
      (node (ref "X1") (pin "3") (pinfunction "3_3") (pintype "passive"))
    )
    (net (code "46") (name "Net-(U1-D-)") (class "Default")
      (node (ref "U1") (pin "5") (pinfunction "D-_5") (pintype "bidirectional"))
      (node (ref "X1") (pin "2") (pinfunction "2_2") (pintype "passive"))
    )
    (net (code "47") (name "Net-(U2-CPH)") (class "Default")
      (node (ref "C2") (pin "2") (pinfunction "2_2") (pintype "passive"))
      (node (ref "U2") (pin "2") (pinfunction "CPH_2") (pintype "power_in"))
    )
    (net (code "48") (name "Net-(U2-CPL)") (class "Default")
      (node (ref "C2") (pin "1") (pinfunction "1_1") (pintype "passive"))
      (node (ref "U2") (pin "1") (pinfunction "CPL_1") (pintype "power_in"))
    )
    (net (code "49") (name "Net-(U2-OUT1)") (class "Default")
      (node (ref "JP1") (pin "1") (pinfunction "1_1") (pintype "passive"))
      (node (ref "TP13") (pin "TP") (pinfunction "TP_TP") (pintype "input"))
      (node (ref "U2") (pin "5") (pinfunction "OUT1_5") (pintype "output"))
    )
    (net (code "50") (name "Net-(U2-OUT2)") (class "Default")
      (node (ref "JP1") (pin "2") (pinfunction "2_2") (pintype "passive"))
      (node (ref "TP12") (pin "TP") (pinfunction "TP_TP") (pintype "input"))
      (node (ref "U2") (pin "8") (pinfunction "OUT2_8") (pintype "output"))
    )
    (net (code "51") (name "Net-(U2-OUT3)") (class "Default")
      (node (ref "JP1") (pin "3") (pinfunction "3_3") (pintype "passive"))
      (node (ref "TP11") (pin "TP") (pinfunction "TP_TP") (pintype "input"))
      (node (ref "U2") (pin "9") (pinfunction "OUT3_9") (pintype "output"))
    )
    (net (code "52") (name "Net-(U2-PGND1)") (class "Default")
      (node (ref "R1") (pin "1") (pinfunction "1_1") (pintype "passive"))
      (node (ref "U2") (pin "10") (pinfunction "PGND3_10") (pintype "power_in"))
      (node (ref "U2") (pin "6") (pinfunction "PGND1_6") (pintype "power_in"))
      (node (ref "U2") (pin "7") (pinfunction "PGND2_7") (pintype "power_in"))
    )
    (net (code "53") (name "Net-(U2-V3P3)") (class "Default")
      (node (ref "C7") (pin "1") (pinfunction "1_1") (pintype "passive"))
      (node (ref "R3") (pin "1") (pinfunction "1_1") (pintype "passive"))
      (node (ref "U2") (pin "15") (pinfunction "V3P3_15") (pintype "power_in"))
    )
    (net (code "54") (name "Net-(U2-VCP)") (class "Default")
      (node (ref "C3") (pin "1") (pinfunction "1_1") (pintype "passive"))
      (node (ref "U2") (pin "3") (pinfunction "VCP_3") (pintype "power_in"))
    )
    (net (code "55") (name "Net-(U3-CPH)") (class "Default")
      (node (ref "C11") (pin "2") (pinfunction "2_2") (pintype "passive"))
      (node (ref "U3") (pin "2") (pinfunction "CPH_2") (pintype "power_in"))
    )
    (net (code "56") (name "Net-(U3-CPL)") (class "Default")
      (node (ref "C11") (pin "1") (pinfunction "1_1") (pintype "passive"))
      (node (ref "U3") (pin "1") (pinfunction "CPL_1") (pintype "power_in"))
    )
    (net (code "57") (name "Net-(U3-IN2)") (class "Default")
      (node (ref "JP9") (pin "1") (pinfunction "1_1") (pintype "passive"))
      (node (ref "TP19") (pin "TP") (pinfunction "TP_TP") (pintype "input"))
      (node (ref "U3") (pin "25") (pinfunction "IN2_25") (pintype "input"))
    )
    (net (code "58") (name "Net-(U3-OUT1)") (class "Default")
      (node (ref "JP3") (pin "1") (pinfunction "1_1") (pintype "passive"))
      (node (ref "TP16") (pin "TP") (pinfunction "TP_TP") (pintype "input"))
      (node (ref "U3") (pin "5") (pinfunction "OUT1_5") (pintype "output"))
    )
    (net (code "59") (name "Net-(U3-OUT2)") (class "Default")
      (node (ref "JP3") (pin "2") (pinfunction "2_2") (pintype "passive"))
      (node (ref "TP15") (pin "TP") (pinfunction "TP_TP") (pintype "input"))
      (node (ref "U3") (pin "8") (pinfunction "OUT2_8") (pintype "output"))
    )
    (net (code "60") (name "Net-(U3-OUT3)") (class "Default")
      (node (ref "JP3") (pin "3") (pinfunction "3_3") (pintype "passive"))
      (node (ref "TP14") (pin "TP") (pinfunction "TP_TP") (pintype "input"))
      (node (ref "U3") (pin "9") (pinfunction "OUT3_9") (pintype "output"))
    )
    (net (code "61") (name "Net-(U3-PGND1)") (class "Default")
      (node (ref "R4") (pin "1") (pinfunction "1_1") (pintype "passive"))
      (node (ref "U3") (pin "10") (pinfunction "PGND3_10") (pintype "power_in"))
      (node (ref "U3") (pin "6") (pinfunction "PGND1_6") (pintype "power_in"))
      (node (ref "U3") (pin "7") (pinfunction "PGND2_7") (pintype "power_in"))
    )
    (net (code "62") (name "Net-(U3-V3P3)") (class "Default")
      (node (ref "C1") (pin "1") (pinfunction "1_1") (pintype "passive"))
      (node (ref "R2") (pin "1") (pinfunction "1_1") (pintype "passive"))
      (node (ref "U3") (pin "15") (pinfunction "V3P3_15") (pintype "power_in"))
    )
    (net (code "63") (name "Net-(U3-VCP)") (class "Default")
      (node (ref "C12") (pin "1") (pinfunction "1_1") (pintype "passive"))
      (node (ref "U3") (pin "3") (pinfunction "VCP_3") (pintype "power_in"))
    )
    (net (code "64") (name "Net-(U5-CB)") (class "Default")
      (node (ref "C19") (pin "1") (pinfunction "1_1") (pintype "passive"))
      (node (ref "U5") (pin "1") (pinfunction "CB_1") (pintype "power_in"))
    )
    (net (code "65") (name "Net-(U5-EN)") (class "Default")
      (node (ref "R5") (pin "1") (pinfunction "1_1") (pintype "passive"))
      (node (ref "R6") (pin "2") (pinfunction "2_2") (pintype "passive"))
      (node (ref "U5") (pin "4") (pinfunction "EN_4") (pintype "input"))
    )
    (net (code "66") (name "Net-(U5-FB)") (class "Default")
      (node (ref "R7") (pin "1") (pinfunction "1_1") (pintype "passive"))
      (node (ref "R8") (pin "2") (pinfunction "2_2") (pintype "passive"))
      (node (ref "U5") (pin "3") (pinfunction "FB_3") (pintype "input"))
    )
    (net (code "67") (name "Net-(U5-GND)") (class "Default")
      (node (ref "C20") (pin "2") (pinfunction "2_2") (pintype "passive"))
      (node (ref "C21") (pin "2") (pinfunction "2_2") (pintype "passive"))
      (node (ref "C22") (pin "2") (pinfunction "2_2") (pintype "passive"))
      (node (ref "R11") (pin "1") (pinfunction "1_1") (pintype "passive"))
      (node (ref "R6") (pin "1") (pinfunction "1_1") (pintype "passive"))
      (node (ref "R8") (pin "1") (pinfunction "1_1") (pintype "passive"))
      (node (ref "U5") (pin "2") (pinfunction "GND_2") (pintype "power_in"))
    )
    (net (code "68") (name "Net-(U5-SW)") (class "Default")
      (node (ref "C19") (pin "2") (pinfunction "2_2") (pintype "passive"))
      (node (ref "L1") (pin "2") (pinfunction "2_2") (pintype "passive"))
      (node (ref "U5") (pin "6") (pinfunction "SW_6") (pintype "power_in"))
    )
    (net (code "69") (name "Net-(U5-VIN)") (class "Default")
      (node (ref "C10") (pin "1") (pinfunction "1_1") (pintype "passive"))
      (node (ref "C20") (pin "1") (pinfunction "1_1") (pintype "passive"))
      (node (ref "C21") (pin "1") (pinfunction "1_1") (pintype "passive"))
      (node (ref "C3") (pin "2") (pinfunction "2_2") (pintype "passive"))
      (node (ref "C8") (pin "1") (pinfunction "1_1") (pintype "passive"))
      (node (ref "C9") (pin "2") (pinfunction "2_2") (pintype "passive"))
      (node (ref "JP2") (pin "2") (pinfunction "2_2") (pintype "passive"))
      (node (ref "R5") (pin "2") (pinfunction "2_2") (pintype "passive"))
      (node (ref "TP3") (pin "TP") (pinfunction "TP_TP") (pintype "input"))
      (node (ref "U2") (pin "11") (pinfunction "VM_11") (pintype "power_in"))
      (node (ref "U2") (pin "4") (pinfunction "VM_4") (pintype "power_in"))
      (node (ref "U5") (pin "5") (pinfunction "VIN_5") (pintype "power_in"))
    )
    (net (code "70") (name "Net-(U6-AD0{slash}SDO)") (class "Default")
      (node (ref "J1") (pin "4") (pinfunction "4_4") (pintype "passive"))
      (node (ref "U6") (pin "9") (pinfunction "AD0/SDO_9") (pintype "output"))
    )
    (net (code "71") (name "Net-(U6-EXP_PAD)") (class "Default")
      (node (ref "C29") (pin "2") (pinfunction "2_2") (pintype "passive"))
      (node (ref "C30") (pin "2") (pinfunction "2_2") (pintype "passive"))
      (node (ref "C31") (pin "2") (pinfunction "2_2") (pintype "passive"))
      (node (ref "J2") (pin "2") (pinfunction "2_2") (pintype "power_in"))
      (node (ref "R10") (pin "1") (pinfunction "1_1") (pintype "passive"))
      (node (ref "U6") (pin "18") (pinfunction "GND_18") (pintype "power_in"))
      (node (ref "U6") (pin "20") (pinfunction "RESV_20_20") (pintype "passive"))
      (node (ref "U6") (pin "25") (pinfunction "EXP_PAD_25") (pintype "power_in"))
    )
    (net (code "72") (name "Net-(U6-REGOUT)") (class "Default")
      (node (ref "C29") (pin "1") (pinfunction "1_1") (pintype "passive"))
      (node (ref "U6") (pin "10") (pinfunction "REGOUT_10") (pintype "output"))
    )
    (net (code "73") (name "Net-(U6-RESV_1)") (class "Default")
      (node (ref "C30") (pin "1") (pinfunction "1_1") (pintype "passive"))
      (node (ref "C31") (pin "1") (pinfunction "1_1") (pintype "passive"))
      (node (ref "LED2") (pin "A") (pinfunction "A_A") (pintype "passive"))
      (node (ref "TP24") (pin "TP") (pinfunction "TP_TP") (pintype "input"))
      (node (ref "U6") (pin "1") (pinfunction "RESV_1_1") (pintype "passive"))
      (node (ref "U6") (pin "13") (pinfunction "VDD_13") (pintype "power_in"))
      (node (ref "U6") (pin "8") (pinfunction "VDDIO_8") (pintype "power_in"))
    )
    (net (code "74") (name "Net-(U6-SCL{slash}SCLK)") (class "Default")
      (node (ref "J1") (pin "2") (pinfunction "2_2") (pintype "power_in"))
      (node (ref "U6") (pin "23") (pinfunction "SCL/SCLK_23") (pintype "input"))
    )
    (net (code "75") (name "Net-(U6-SDA{slash}SDI)") (class "Default")
      (node (ref "J1") (pin "3") (pinfunction "3_3") (pintype "passive"))
      (node (ref "U6") (pin "24") (pinfunction "SDA/SDI_24") (pintype "bidirectional"))
    )
    (net (code "76") (name "Net-(U6-~{CS})") (class "Default")
      (node (ref "J1") (pin "1") (pinfunction "1_1") (pintype "power_in"))
      (node (ref "U6") (pin "22") (pinfunction "~{CS}_22") (pintype "input"))
    )
    (net (code "77") (name "VCC") (class "Default")
      (node (ref "C17") (pin "1") (pinfunction "1_1") (pintype "passive"))
      (node (ref "LED1") (pin "A") (pinfunction "A_A") (pintype "passive"))
      (node (ref "U1") (pin "7") (pinfunction "REGIN_7") (pintype "passive"))
      (node (ref "U1") (pin "8") (pinfunction "VBUS_8") (pintype "input"))
      (node (ref "X1") (pin "1") (pinfunction "1_1") (pintype "passive"))
    )
    (net (code "78") (name "unconnected-(IC2A-OSC_IN-Pad5)") (class "Default")
      (node (ref "IC2") (pin "5") (pinfunction "OSC_IN_5") (pintype "bidirectional"))
    )
    (net (code "79") (name "unconnected-(IC2A-OSC_OUT-Pad6)") (class "Default")
      (node (ref "IC2") (pin "6") (pinfunction "OSC_OUT_6") (pintype "bidirectional"))
    )
    (net (code "80") (name "unconnected-(IC2A-PA0-WKUP-Pad10)") (class "Default")
      (node (ref "IC2") (pin "10") (pinfunction "PA0-WKUP_10") (pintype "bidirectional"))
    )
    (net (code "81") (name "unconnected-(IC2A-PA8-Pad29)") (class "Default")
      (node (ref "IC2") (pin "29") (pinfunction "PA8_29") (pintype "bidirectional"))
    )
    (net (code "82") (name "unconnected-(IC2A-PA12-Pad33)") (class "Default")
      (node (ref "IC2") (pin "33") (pinfunction "PA12_33") (pintype "bidirectional"))
    )
    (net (code "83") (name "unconnected-(IC2A-PA15-Pad38)") (class "Default")
      (node (ref "IC2") (pin "38") (pinfunction "PA15_38") (pintype "bidirectional"))
    )
    (net (code "84") (name "unconnected-(IC2A-PC13-Pad2)") (class "Default")
      (node (ref "IC2") (pin "2") (pinfunction "PC13_2") (pintype "bidirectional"))
    )
    (net (code "85") (name "unconnected-(IC2A-PC14-Pad3)") (class "Default")
      (node (ref "IC2") (pin "3") (pinfunction "PC14_3") (pintype "bidirectional"))
    )
    (net (code "86") (name "unconnected-(IC2A-PC15-Pad4)") (class "Default")
      (node (ref "IC2") (pin "4") (pinfunction "PC15_4") (pintype "bidirectional"))
    )
    (net (code "87") (name "unconnected-(J2-Pad1)") (class "Default")
      (node (ref "J2") (pin "1") (pinfunction "1_1") (pintype "power_in"))
    )
    (net (code "88") (name "unconnected-(J2-Pad4)") (class "Default")
      (node (ref "J2") (pin "4") (pinfunction "4_4") (pintype "passive"))
    )
    (net (code "89") (name "unconnected-(U1-CTS-Pad23)") (class "Default")
      (node (ref "U1") (pin "23") (pinfunction "CTS_23") (pintype "input"))
    )
    (net (code "90") (name "unconnected-(U1-DCD-Pad1)") (class "Default")
      (node (ref "U1") (pin "1") (pinfunction "DCD_1") (pintype "input"))
    )
    (net (code "91") (name "unconnected-(U1-DSR-Pad27)") (class "Default")
      (node (ref "U1") (pin "27") (pinfunction "DSR_27") (pintype "input"))
    )
    (net (code "92") (name "unconnected-(U1-DTR-Pad28)") (class "Default")
      (node (ref "U1") (pin "28") (pinfunction "DTR_28") (pintype "output"))
    )
    (net (code "93") (name "unconnected-(U1-RI-Pad2)") (class "Default")
      (node (ref "U1") (pin "2") (pinfunction "RI_2") (pintype "input"))
    )
    (net (code "94") (name "unconnected-(U1-RTS-Pad24)") (class "Default")
      (node (ref "U1") (pin "24") (pinfunction "RTS_24") (pintype "output"))
    )
    (net (code "95") (name "unconnected-(U1-SUSPEND-Pad12)") (class "Default")
      (node (ref "U1") (pin "12") (pinfunction "SUSPEND_12") (pintype "output"))
    )
    (net (code "96") (name "unconnected-(U1-~{SUSPEND}-Pad11)") (class "Default")
      (node (ref "U1") (pin "11") (pinfunction "~{SUSPEND}_11") (pintype "output"))
    )
    (net (code "97") (name "unconnected-(U2-NC-Pad21)") (class "Default")
      (node (ref "U2") (pin "21") (pinfunction "NC_21") (pintype "no_connect"))
    )
    (net (code "98") (name "unconnected-(U3-NC-Pad21)") (class "Default")
      (node (ref "U3") (pin "21") (pinfunction "NC_21") (pintype "no_connect"))
    )
    (net (code "99") (name "unconnected-(U6-AUX_CL-Pad7)") (class "Default")
      (node (ref "U6") (pin "7") (pinfunction "AUX_CL_7") (pintype "input"))
    )
    (net (code "100") (name "unconnected-(U6-AUX_DA-Pad21)") (class "Default")
      (node (ref "U6") (pin "21") (pinfunction "AUX_DA_21") (pintype "input"))
    )
    (net (code "101") (name "unconnected-(U6-RESV_19-Pad19)") (class "Default")
      (node (ref "U6") (pin "19") (pinfunction "RESV_19_19") (pintype "passive"))
    )
  )
)
